# sustentationAvecPC.net
KiCad netlist of a schematic drawn in Altium Designer
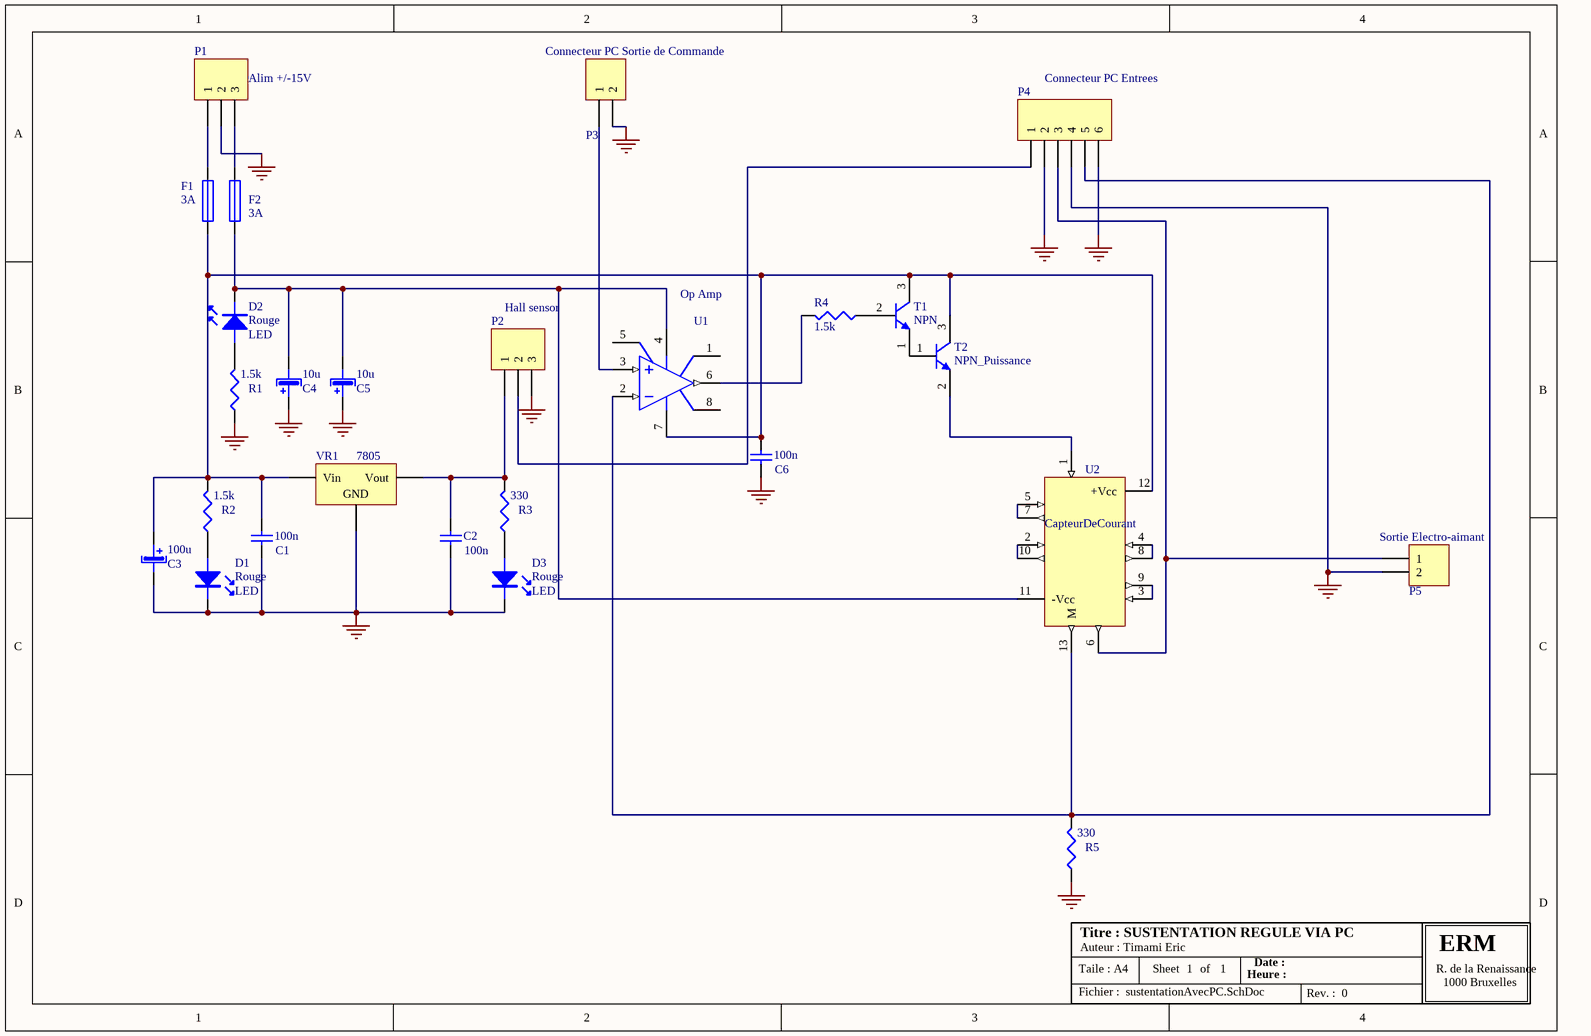
[diagram p0: sustentationAvecPC.SchDoc]

(export (version "E")
  (design (tool "Eeschema 10.0.6"))
  (components
    (comp (ref "C1")
      (value "100n")
      (footprint "Capa_100n")
      (description "Condensateur")
      (fields (field (name "DESIGNER") "ECAM 2004"))
      (libsource (lib "AntiNuisibles") (part "Condensateur"))
    )
    (comp (ref "C2")
      (value "100n")
      (footprint "Capa_100n")
      (description "Condensateur")
      (fields (field (name "DESIGNER") "ECAM 2004"))
      (libsource (lib "sustentationAvecPC") (part "Condensateur"))
    )
    (comp (ref "C3")
      (value "100u")
      (footprint "AXIAL-1.0")
      (description "Condensateur polatisé")
      (fields (field (name "Comment") "Cond pol radial") (field (name "DESIGNER") "ECAM 2004"))
      (libsource (lib "sustentationAvecPC") (part "Cond pol radial"))
    )
    (comp (ref "C4")
      (value "10u")
      (footprint "CAPPR_100u")
      (description "Condensateur polatisé")
      (fields (field (name "Comment") "Cond pol radial") (field (name "DESIGNER") "ECAM 2004"))
      (libsource (lib "sustentationAvecPC") (part "Cond pol radial"))
    )
    (comp (ref "C5")
      (value "10u")
      (footprint "CAPPR_100u")
      (description "Condensateur polatisé")
      (fields (field (name "Comment") "Cond pol  rad") (field (name "DESIGNER") "ECAM 2004"))
      (libsource (lib "sustentationAvecPC") (part "Cond pol radial"))
    )
    (comp (ref "C6")
      (value "100n")
      (footprint "Capa_100n")
      (description "Condensateur")
      (fields (field (name "DESIGNER") "ECAM 2004"))
      (libsource (lib "sustentationAvecPC") (part "Condensateur"))
    )
    (comp (ref "D1")
      (value "LED")
      (footprint "Led 0.1")
      (fields (field (name "COLOR") "Rouge") (field (name "DESIGNER") "ECAM 2004"))
      (libsource (lib "sustentationAvecPC") (part "LED"))
    )
    (comp (ref "D2")
      (value "LED")
      (footprint "Led 0.1")
      (fields (field (name "COLOR") "Rouge") (field (name "DESIGNER") "ECAM 2004"))
      (libsource (lib "sustentationAvecPC") (part "LED"))
    )
    (comp (ref "D3")
      (value "LED")
      (footprint "Led 0.1")
      (fields (field (name "COLOR") "Rouge") (field (name "DESIGNER") "ECAM 2004"))
      (libsource (lib "sustentationAvecPC") (part "LED"))
    )
    (comp (ref "F1")
      (value "3A")
      (footprint "FUSE-10")
      (description "Fusible")
      (fields (field (name "DESIGNER") "ECAM 2004"))
      (libsource (lib "*") (part "Fusible"))
    )
    (comp (ref "F2")
      (value "3A")
      (footprint "FUSE-10")
      (description "Fusible")
      (fields (field (name "DESIGNER") "ECAM 2004"))
      (libsource (lib "*") (part "Fusible"))
    )
    (comp (ref "P1")
      (value "Alim +/-15V")
      (footprint "CONVIS-3")
      (description "Header, 3-Pin")
      (fields (field (name "PUBLISHER") "Altium Limited"))
      (libsource (lib "sustentationAvecPC") (part "connecteur 3"))
    )
    (comp (ref "P2")
      (value "Hall sensor")
      (footprint "connecteur capteur Hall")
      (description "Header, 3-Pin")
      (fields (field (name "PUBLISHER") "Altium Limited"))
      (libsource (lib "sustentationAvecPC") (part "connecteur 3"))
    )
    (comp (ref "P3")
      (value "Connecteur PC Sortie de Commande")
      (footprint "connecteur PC Sorties command")
      (description "Connecteur")
      (fields (field (name "DESIGNER") "ECAM 2005"))
      (libsource (lib "") (part "Connecteur 2_1"))
    )
    (comp (ref "P4")
      (value "Connecteur PC Entrees")
      (footprint "connecteur PC Entrées")
      (description "Header, 6-Pin")
      (fields (field (name "PUBLISHER") "Altium Limited"))
      (libsource (lib "sustentationAvecPC") (part "Header 6"))
    )
    (comp (ref "P5")
      (value "Sortie Electro-aimant")
      (footprint "connecteur 3A")
      (description "Connecteur")
      (fields (field (name "DESIGNER") "ECAM 2005"))
      (libsource (lib "sustentationAvecPC") (part "Connecteur 2"))
    )
    (comp (ref "R1")
      (value "1.5k")
      (footprint "AXIAL-0.4")
      (description "Résistance standard")
      (fields (field (name "Comment") "Résistance") (field (name "DESIGNER") "ECAM 2005"))
      (libsource (lib "sustentationAvecPC") (part "Résistance"))
    )
    (comp (ref "R2")
      (value "1.5k")
      (footprint "AXIAL-0.4")
      (description "Résistance standard")
      (fields (field (name "Comment") "Résistance") (field (name "DESIGNER") "ECAM 2005"))
      (libsource (lib "sustentationAvecPC") (part "Résistance"))
    )
    (comp (ref "R3")
      (value "330")
      (footprint "AXIAL-0.4")
      (description "Résistance standard")
      (fields (field (name "Comment") "Résistance") (field (name "DESIGNER") "ECAM 2005"))
      (libsource (lib "sustentationAvecPC") (part "Résistance"))
    )
    (comp (ref "R4")
      (value "1.5k")
      (footprint "AXIAL-0.4")
      (description "Résistance standard")
      (fields (field (name "Comment") "Résistance") (field (name "DESIGNER") "ECAM 2005"))
      (libsource (lib "sustentationAvecPC") (part "Résistance"))
    )
    (comp (ref "R5")
      (value "330")
      (footprint "AXIAL-0.4")
      (description "Résistance standard")
      (fields (field (name "Comment") "Résistance") (field (name "DESIGNER") "ECAM 2005"))
      (libsource (lib "sustentationAvecPC") (part "Résistance"))
    )
    (comp (ref "T1")
      (value "NPN")
      (footprint "TO-5")
      (description "NPN Bipolar Transistor")
      (fields (field (name "PUBLISHER") "Altium Limited"))
      (libsource (lib "sustentationAvecPC") (part "NPN"))
    )
    (comp (ref "T2")
      (value "NPN_Puissance")
      (footprint "TO-3")
      (description "NPN Bipolar Transistor")
      (fields (field (name "PUBLISHER") "Altium Limited"))
      (libsource (lib "sustentationAvecPC") (part "NPN_Puissance"))
    )
    (comp (ref "U1")
      (value "Op Amp")
      (footprint "DIP8")
      (description "FET Operational Amplifier")
      (fields (field (name "PUBLISHER") "Altium Limited"))
      (libsource (lib "sustentationAvecPC") (part "Op Amp"))
    )
    (comp (ref "U2")
      (value "CapteurDeCourant")
      (footprint "Sonde_Courant")
      (fields (field (name "PUBLISHER") "Altium Limited"))
      (libsource (lib "sustentationAvecPC") (part "CapteurDeCourant"))
    )
    (comp (ref "VR1")
      (value "7805")
      (footprint "TO-220 regulateur")
      (description "Voltage Regulator")
      (fields (field (name "PUBLISHER") "Altium Limited"))
      (libsource (lib "sustentationAvecPC") (part "Volt Reg"))
    )
  )
  (nets
    (net (code "1") (name "GND") (class "Default")
      (node (ref "C1") (pin "2") (pinfunction "2_2") (pintype "passive"))
      (node (ref "C2") (pin "2") (pinfunction "2_2") (pintype "passive"))
      (node (ref "C3") (pin "2") (pinfunction "-_2") (pintype "passive"))
      (node (ref "C4") (pin "1") (pinfunction "+_1") (pintype "passive"))
      (node (ref "C5") (pin "1") (pinfunction "+_1") (pintype "passive"))
      (node (ref "C6") (pin "2") (pinfunction "2_2") (pintype "passive"))
      (node (ref "D1") (pin "2") (pinfunction "K_2") (pintype "passive"))
      (node (ref "D3") (pin "2") (pinfunction "K_2") (pintype "passive"))
      (node (ref "P1") (pin "2") (pinfunction "2_2") (pintype "passive"))
      (node (ref "P2") (pin "3") (pinfunction "3_3") (pintype "passive"))
      (node (ref "P3") (pin "2") (pinfunction "2_2") (pintype "passive"))
      (node (ref "P4") (pin "2") (pinfunction "2_2") (pintype "passive"))
      (node (ref "P4") (pin "4") (pinfunction "4_4") (pintype "passive"))
      (node (ref "P4") (pin "6") (pinfunction "6_6") (pintype "passive"))
      (node (ref "P5") (pin "2") (pinfunction "2_2") (pintype "passive"))
      (node (ref "R1") (pin "1") (pinfunction "1_1") (pintype "passive"))
      (node (ref "R5") (pin "1") (pinfunction "1_1") (pintype "passive"))
      (node (ref "VR1") (pin "2") (pinfunction "GND_2") (pintype "passive"))
    )
    (net (code "2") (name "Net-(C3-+)") (class "Default")
      (node (ref "C1") (pin "1") (pinfunction "1_1") (pintype "passive"))
      (node (ref "C3") (pin "1") (pinfunction "+_1") (pintype "passive"))
      (node (ref "C6") (pin "1") (pinfunction "1_1") (pintype "passive"))
      (node (ref "F1") (pin "2") (pinfunction "F2_2") (pintype "passive"))
      (node (ref "R2") (pin "2") (pinfunction "2_2") (pintype "passive"))
      (node (ref "T1") (pin "3") (pinfunction "C_3") (pintype "passive"))
      (node (ref "T2") (pin "3") (pinfunction "C_3") (pintype "passive"))
      (node (ref "U1") (pin "7") (pinfunction "V+_7") (pintype "power_in"))
      (node (ref "U2") (pin "12") (pinfunction "+Vcc_12") (pintype "power_in"))
      (node (ref "VR1") (pin "1") (pinfunction "Vin_1") (pintype "passive"))
    )
    (net (code "3") (name "Net-(C4--)") (class "Default")
      (node (ref "C4") (pin "2") (pinfunction "-_2") (pintype "passive"))
      (node (ref "C5") (pin "2") (pinfunction "-_2") (pintype "passive"))
      (node (ref "D2") (pin "2") (pinfunction "K_2") (pintype "passive"))
      (node (ref "F2") (pin "2") (pinfunction "F2_2") (pintype "passive"))
      (node (ref "U1") (pin "4") (pinfunction "V-_4") (pintype "power_in"))
      (node (ref "U2") (pin "11") (pinfunction "-Vcc_11") (pintype "power_in"))
    )
    (net (code "4") (name "Net-(D1-A)") (class "Default")
      (node (ref "D1") (pin "1") (pinfunction "A_1") (pintype "passive"))
      (node (ref "R2") (pin "1") (pinfunction "1_1") (pintype "passive"))
    )
    (net (code "5") (name "Net-(D2-A)") (class "Default")
      (node (ref "D2") (pin "1") (pinfunction "A_1") (pintype "passive"))
      (node (ref "R1") (pin "2") (pinfunction "2_2") (pintype "passive"))
    )
    (net (code "6") (name "Net-(D3-A)") (class "Default")
      (node (ref "D3") (pin "1") (pinfunction "A_1") (pintype "passive"))
      (node (ref "R3") (pin "1") (pinfunction "1_1") (pintype "passive"))
    )
    (net (code "7") (name "Net-(F1-F1)") (class "Default")
      (node (ref "F1") (pin "1") (pinfunction "F1_1") (pintype "passive"))
      (node (ref "P1") (pin "1") (pinfunction "1_1") (pintype "passive"))
    )
    (net (code "8") (name "Net-(F2-F1)") (class "Default")
      (node (ref "F2") (pin "1") (pinfunction "F1_1") (pintype "passive"))
      (node (ref "P1") (pin "3") (pinfunction "3_3") (pintype "passive"))
    )
    (net (code "9") (name "Net-(P2-Pad2)") (class "Default")
      (node (ref "P2") (pin "2") (pinfunction "2_2") (pintype "passive"))
      (node (ref "P4") (pin "1") (pinfunction "1_1") (pintype "passive"))
    )
    (net (code "10") (name "Net-(P4-Pad3)") (class "Default")
      (node (ref "P4") (pin "3") (pinfunction "3_3") (pintype "passive"))
      (node (ref "P5") (pin "1") (pinfunction "1_1") (pintype "passive"))
      (node (ref "U2") (pin "6") (pintype "output"))
    )
    (net (code "11") (name "Net-(T1-B)") (class "Default")
      (node (ref "R4") (pin "1") (pinfunction "1_1") (pintype "passive"))
      (node (ref "T1") (pin "2") (pinfunction "B_2") (pintype "passive"))
    )
    (net (code "12") (name "Net-(T1-E)") (class "Default")
      (node (ref "T1") (pin "1") (pinfunction "E_1") (pintype "passive"))
      (node (ref "T2") (pin "1") (pinfunction "B_1") (pintype "passive"))
    )
    (net (code "13") (name "Net-(T2-E)") (class "Default")
      (node (ref "T2") (pin "2") (pinfunction "E_2") (pintype "passive"))
      (node (ref "U2") (pin "1") (pintype "input"))
    )
    (net (code "14") (name "Net-(U1-IN+)") (class "Default")
      (node (ref "P3") (pin "1") (pinfunction "1_1") (pintype "passive"))
      (node (ref "U1") (pin "3") (pinfunction "IN+_3") (pintype "input"))
    )
    (net (code "15") (name "Net-(U1-IN-)") (class "Default")
      (node (ref "P4") (pin "5") (pinfunction "5_5") (pintype "passive"))
      (node (ref "R5") (pin "2") (pinfunction "2_2") (pintype "passive"))
      (node (ref "U1") (pin "2") (pinfunction "IN-_2") (pintype "input"))
      (node (ref "U2") (pin "13") (pinfunction "M_13") (pintype "output"))
    )
    (net (code "16") (name "Net-(U1-OUT)") (class "Default")
      (node (ref "R4") (pin "2") (pinfunction "2_2") (pintype "passive"))
      (node (ref "U1") (pin "6") (pinfunction "OUT_6") (pintype "output"))
    )
    (net (code "17") (name "Net-(U2-Pad3)") (class "Default")
      (node (ref "U2") (pin "3") (pintype "input"))
      (node (ref "U2") (pin "9") (pintype "output"))
    )
    (net (code "18") (name "Net-(U2-Pad4)") (class "Default")
      (node (ref "U2") (pin "4") (pintype "input"))
      (node (ref "U2") (pin "8") (pintype "output"))
    )
    (net (code "19") (name "Net-(U2-Pad5)") (class "Default")
      (node (ref "U2") (pin "5") (pintype "input"))
      (node (ref "U2") (pin "7") (pintype "output"))
    )
    (net (code "20") (name "Net-(U2-Pad10)") (class "Default")
      (node (ref "U2") (pin "10") (pintype "output"))
      (node (ref "U2") (pin "2") (pintype "input"))
    )
    (net (code "21") (name "Net-(VR1-Vout)") (class "Default")
      (node (ref "C2") (pin "1") (pinfunction "1_1") (pintype "passive"))
      (node (ref "P2") (pin "1") (pinfunction "1_1") (pintype "passive"))
      (node (ref "R3") (pin "2") (pinfunction "2_2") (pintype "passive"))
      (node (ref "VR1") (pin "3") (pinfunction "Vout_3") (pintype "passive"))
    )
    (net (code "22") (name "unconnected-(U1-OS_NUL-Pad1)") (class "Default")
      (node (ref "U1") (pin "1") (pinfunction "OS_NUL_1") (pintype "passive"))
    )
    (net (code "23") (name "unconnected-(U1-OS_NUL-Pad5)") (class "Default")
      (node (ref "U1") (pin "5") (pinfunction "OS_NUL_5") (pintype "passive"))
    )
    (net (code "24") (name "unconnected-(U1-TAB-Pad8)") (class "Default")
      (node (ref "U1") (pin "8") (pinfunction "TAB_8") (pintype "passive"))
    )
  )
)
